# PathFinder_1.net
KiCad netlist of a schematic drawn in EasyEDA Pro
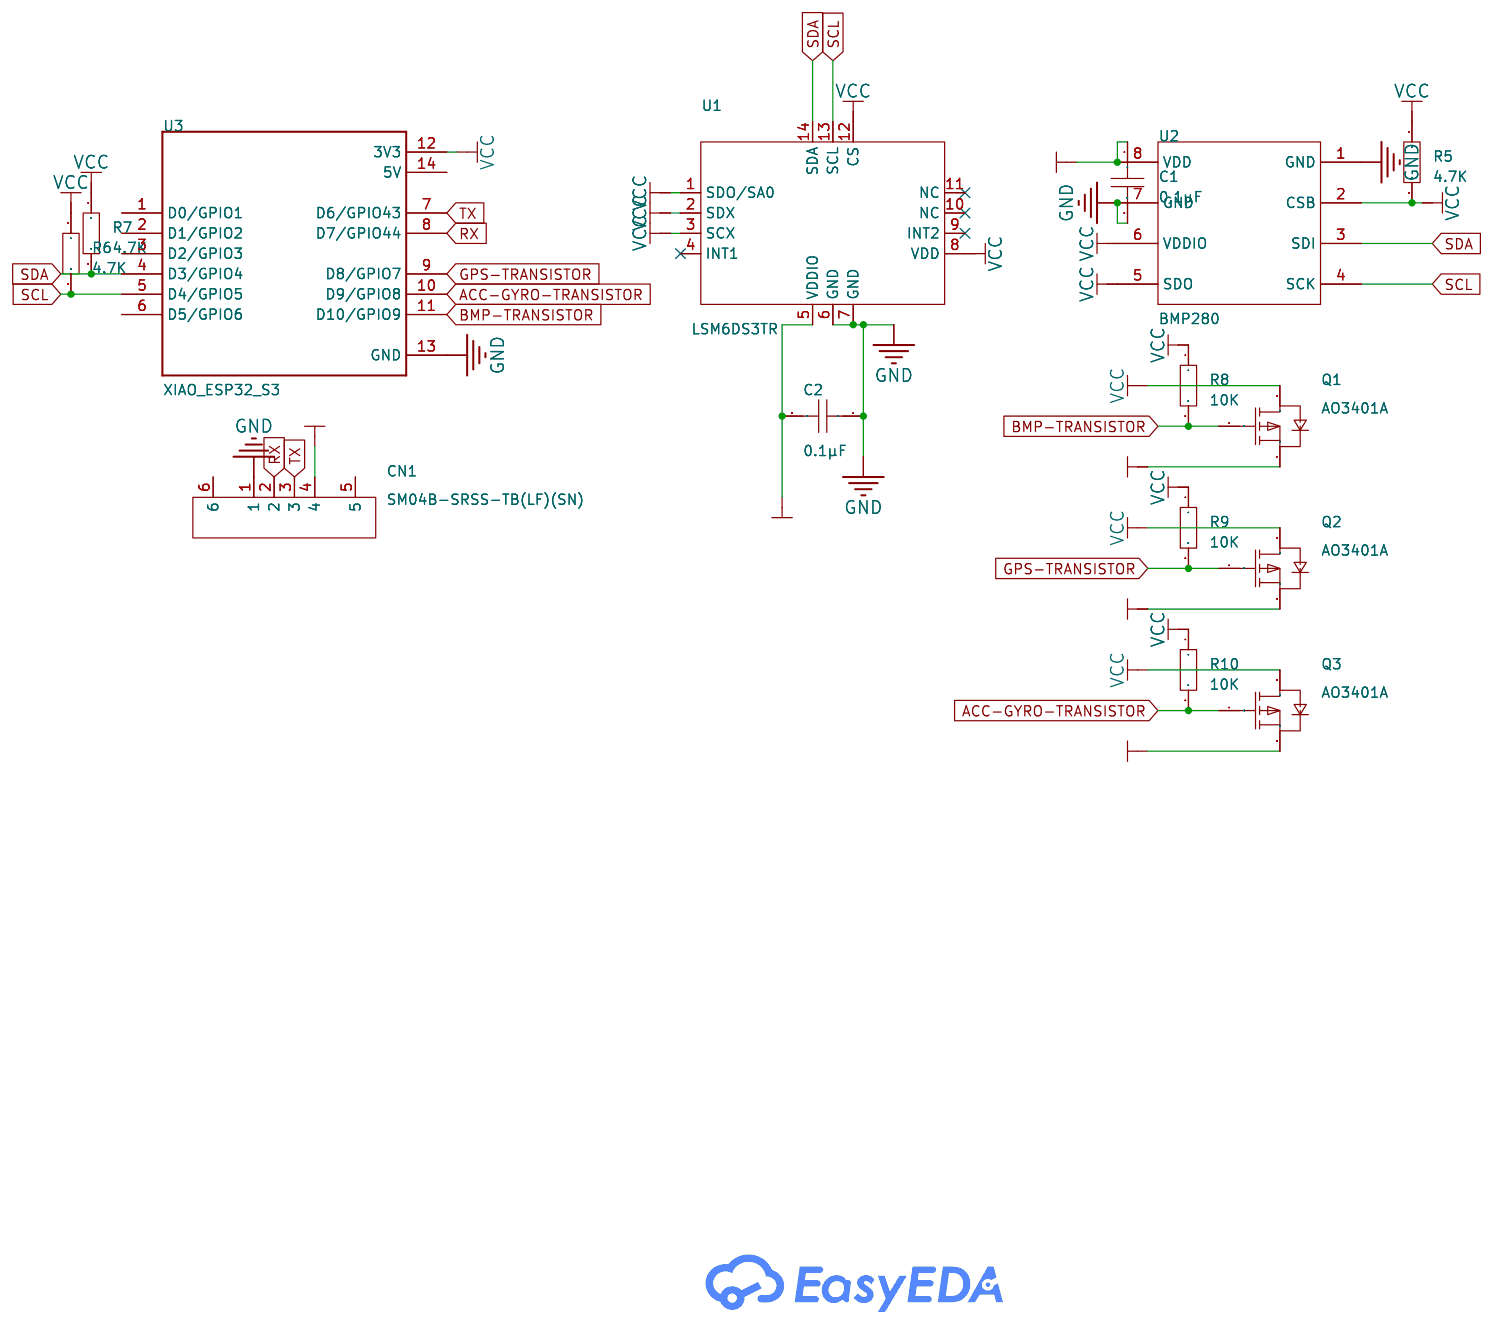
[diagram p0: schematic sheet]

(export (version "E")
  (design (tool "Eeschema 10.0.6"))
  (components
    (comp (ref "C1")
      (value "100nF")
      (footprint "easyedapro:C0603")
      (libsource (lib "easyedapro") (part "CAP"))
    )
    (comp (ref "C2")
      (value "100nF")
      (footprint "easyedapro:C0603")
      (libsource (lib "easyedapro") (part "CAP"))
    )
    (comp (ref "CN1")
      (value "SM04B-SRSS-TB(LF)(SN)")
      (footprint "easyedapro:CONN-SMD_4P-P1.00_SM04B-SRSS-TB-LF-SN")
      (fields (field (name "Manufacturer") "JST"))
      (libsource (lib "easyedapro") (part "SM04B-SRSS-TB (LF)(SN)"))
    )
    (comp (ref "Q1")
      (value "AO3401A")
      (footprint "easyedapro:SOT-23-3_L2.9-W1.3-P1.90-LS2.4-BR")
      (fields (field (name "Manufacturer") "YTL(亚特联)"))
      (libsource (lib "easyedapro") (part "AO3401A_C53477312"))
    )
    (comp (ref "Q2")
      (value "AO3401A")
      (footprint "easyedapro:SOT-23-3_L2.9-W1.3-P1.90-LS2.4-BR")
      (fields (field (name "Manufacturer") "YTL(亚特联)"))
      (libsource (lib "easyedapro") (part "AO3401A_C53477312"))
    )
    (comp (ref "Q3")
      (value "AO3401A")
      (footprint "easyedapro:SOT-23-3_L2.9-W1.3-P1.90-LS2.4-BR")
      (fields (field (name "Manufacturer") "YTL(亚特联)"))
      (libsource (lib "easyedapro") (part "AO3401A_C53477312"))
    )
    (comp (ref "R5") (value "10K") (footprint "easyedapro:R0603") (libsource (lib "easyedapro") (part "Res")))
    (comp (ref "R6") (value "10K") (footprint "easyedapro:R0603") (libsource (lib "easyedapro") (part "Res")))
    (comp (ref "R7") (value "10K") (footprint "easyedapro:R0603") (libsource (lib "easyedapro") (part "Res")))
    (comp (ref "R8") (value "10K") (footprint "easyedapro:R0603") (libsource (lib "easyedapro") (part "Res")))
    (comp (ref "R9") (value "10K") (footprint "easyedapro:R0603") (libsource (lib "easyedapro") (part "Res")))
    (comp (ref "R10")
      (value "10K")
      (footprint "easyedapro:R0603")
      (libsource (lib "easyedapro") (part "Res"))
    )
    (comp (ref "U1")
      (value "LSM6DS3TR")
      (footprint "easyedapro:LGA-14_L3.0-W2.5-P0.50-TL")
      (fields (field (name "Manufacturer") "ST(意法半导体)"))
      (libsource (lib "easyedapro") (part "LSM6DS3TR"))
    )
    (comp (ref "U2")
      (value "BMP280")
      (footprint "easyedapro:LGA-8_L2.5-W2.0-P0.65_AMP6127")
      (fields (field (name "Manufacturer") "Bosch(博世)"))
      (libsource (lib "easyedapro") (part "BMP280"))
    )
    (comp (ref "U3")
      (value "XIAO_ESP32_S3")
      (footprint "easyedapro:MODULE_XIAO_ESP32_S3")
      (libsource (lib "easyedapro") (part "XIAO_ESP32_S3"))
    )
  )
  (nets
    (net (code "1") (name "ACC-GYRO-TRANSISTOR") (class "Default")
      (node (ref "Q3") (pin "1") (pinfunction "G_1") (pintype "unspecified"))
      (node (ref "R10") (pin "2") (pinfunction "2_2") (pintype "input"))
      (node (ref "U3") (pin "10") (pinfunction "D9/GPIO8_10") (pintype "bidirectional"))
    )
    (net (code "2") (name "BMP-TRANSISTOR") (class "Default")
      (node (ref "Q1") (pin "1") (pinfunction "G_1") (pintype "unspecified"))
      (node (ref "R8") (pin "2") (pinfunction "2_2") (pintype "input"))
      (node (ref "U3") (pin "11") (pinfunction "D10/GPIO9_11") (pintype "bidirectional"))
    )
    (net (code "3") (name "GND") (class "Default")
      (node (ref "C1") (pin "2") (pinfunction "2_2") (pintype "input"))
      (node (ref "C2") (pin "1") (pinfunction "1_1") (pintype "input"))
      (node (ref "CN1") (pin "1") (pinfunction "1_1") (pintype "unspecified"))
      (node (ref "U1") (pin "6") (pinfunction "GND_6") (pintype "unspecified"))
      (node (ref "U1") (pin "7") (pinfunction "GND_7") (pintype "unspecified"))
      (node (ref "U2") (pin "1") (pinfunction "GND_1") (pintype "unspecified"))
      (node (ref "U2") (pin "7") (pinfunction "GND_7") (pintype "unspecified"))
      (node (ref "U3") (pin "13") (pinfunction "GND_13") (pintype "unspecified"))
    )
    (net (code "4") (name "GPS-TRANSISTOR") (class "Default")
      (node (ref "Q2") (pin "1") (pinfunction "G_1") (pintype "unspecified"))
      (node (ref "R9") (pin "2") (pinfunction "2_2") (pintype "input"))
      (node (ref "U3") (pin "9") (pinfunction "D8/GPIO7_9") (pintype "bidirectional"))
    )
    (net (code "5") (name "RX") (class "Default")
      (node (ref "CN1") (pin "2") (pinfunction "2_2") (pintype "unspecified"))
      (node (ref "U3") (pin "8") (pinfunction "D7/GPIO44_8") (pintype "bidirectional"))
    )
    (net (code "6") (name "SCL") (class "Default")
      (node (ref "R6") (pin "2") (pinfunction "2_2") (pintype "input"))
      (node (ref "U1") (pin "13") (pinfunction "SCL_13") (pintype "unspecified"))
      (node (ref "U2") (pin "4") (pinfunction "SCK_4") (pintype "unspecified"))
      (node (ref "U3") (pin "5") (pinfunction "D4/GPIO5_5") (pintype "bidirectional"))
    )
    (net (code "7") (name "SDA") (class "Default")
      (node (ref "R7") (pin "2") (pinfunction "2_2") (pintype "input"))
      (node (ref "U1") (pin "14") (pinfunction "SDA_14") (pintype "unspecified"))
      (node (ref "U2") (pin "3") (pinfunction "SDI_3") (pintype "unspecified"))
      (node (ref "U3") (pin "4") (pinfunction "D3/GPIO4_4") (pintype "bidirectional"))
    )
    (net (code "8") (name "TX") (class "Default")
      (node (ref "CN1") (pin "3") (pinfunction "3_3") (pintype "unspecified"))
      (node (ref "U3") (pin "7") (pinfunction "D6/GPIO43_7") (pintype "bidirectional"))
    )
    (net (code "9") (name "VCC") (class "Default")
      (node (ref "Q1") (pin "3") (pinfunction "D_3") (pintype "unspecified"))
      (node (ref "Q2") (pin "3") (pinfunction "D_3") (pintype "unspecified"))
      (node (ref "Q3") (pin "3") (pinfunction "D_3") (pintype "unspecified"))
      (node (ref "R10") (pin "1") (pinfunction "1_1") (pintype "input"))
      (node (ref "R5") (pin "1") (pinfunction "1_1") (pintype "input"))
      (node (ref "R5") (pin "2") (pinfunction "2_2") (pintype "input"))
      (node (ref "R6") (pin "1") (pinfunction "1_1") (pintype "input"))
      (node (ref "R7") (pin "1") (pinfunction "1_1") (pintype "input"))
      (node (ref "R8") (pin "1") (pinfunction "1_1") (pintype "input"))
      (node (ref "R9") (pin "1") (pinfunction "1_1") (pintype "input"))
      (node (ref "U1") (pin "1") (pinfunction "SDO/SA0_1") (pintype "unspecified"))
      (node (ref "U1") (pin "12") (pinfunction "CS_12") (pintype "unspecified"))
      (node (ref "U1") (pin "2") (pinfunction "SDX_2") (pintype "unspecified"))
      (node (ref "U1") (pin "3") (pinfunction "SCX_3") (pintype "unspecified"))
      (node (ref "U1") (pin "8") (pinfunction "VDD_8") (pintype "unspecified"))
      (node (ref "U2") (pin "2") (pinfunction "CSB_2") (pintype "unspecified"))
      (node (ref "U2") (pin "5") (pinfunction "SDO_5") (pintype "unspecified"))
      (node (ref "U2") (pin "6") (pinfunction "VDDIO_6") (pintype "unspecified"))
      (node (ref "U3") (pin "12") (pinfunction "3V3_12") (pintype "unspecified"))
    )
    (net (code "10") (name "VCC-BMP") (class "Default")
      (node (ref "C1") (pin "1") (pinfunction "1_1") (pintype "input"))
      (node (ref "Q1") (pin "2") (pinfunction "S_2") (pintype "unspecified"))
      (node (ref "U2") (pin "8") (pinfunction "VDD_8") (pintype "unspecified"))
    )
    (net (code "11") (name "VCC-GPS") (class "Default")
      (node (ref "CN1") (pin "4") (pinfunction "4_4") (pintype "unspecified"))
      (node (ref "Q2") (pin "2") (pinfunction "S_2") (pintype "unspecified"))
    )
    (net (code "12") (name "VCC-GYRO-ACC") (class "Default")
      (node (ref "C2") (pin "2") (pinfunction "2_2") (pintype "input"))
      (node (ref "Q3") (pin "2") (pinfunction "S_2") (pintype "unspecified"))
      (node (ref "U1") (pin "5") (pinfunction "VDDIO_5") (pintype "unspecified"))
    )
    (net (code "13") (name "unconnected-(CN1-Pad5)") (class "Default")
      (node (ref "CN1") (pin "5") (pinfunction "5_5") (pintype "unspecified"))
    )
    (net (code "14") (name "unconnected-(CN1-Pad6)") (class "Default")
      (node (ref "CN1") (pin "6") (pinfunction "6_6") (pintype "unspecified"))
    )
    (net (code "15") (name "unconnected-(U1-INT1-Pad4)") (class "Default")
      (node (ref "U1") (pin "4") (pinfunction "INT1_4") (pintype "unspecified+no_connect"))
    )
    (net (code "16") (name "unconnected-(U1-INT2-Pad9)") (class "Default")
      (node (ref "U1") (pin "9") (pinfunction "INT2_9") (pintype "unspecified+no_connect"))
    )
    (net (code "17") (name "unconnected-(U1-NC-Pad10)") (class "Default")
      (node (ref "U1") (pin "10") (pinfunction "NC_10") (pintype "unspecified+no_connect"))
    )
    (net (code "18") (name "unconnected-(U1-NC-Pad11)") (class "Default")
      (node (ref "U1") (pin "11") (pinfunction "NC_11") (pintype "unspecified+no_connect"))
    )
    (net (code "19") (name "unconnected-(U3-5V-Pad14)") (class "Default")
      (node (ref "U3") (pin "14") (pinfunction "5V_14") (pintype "unspecified"))
    )
    (net (code "20") (name "unconnected-(U3-D0{slash}GPIO1-Pad1)") (class "Default")
      (node (ref "U3") (pin "1") (pinfunction "D0/GPIO1_1") (pintype "bidirectional"))
    )
    (net (code "21") (name "unconnected-(U3-D1{slash}GPIO2-Pad2)") (class "Default")
      (node (ref "U3") (pin "2") (pinfunction "D1/GPIO2_2") (pintype "bidirectional"))
    )
    (net (code "22") (name "unconnected-(U3-D2{slash}GPIO3-Pad3)") (class "Default")
      (node (ref "U3") (pin "3") (pinfunction "D2/GPIO3_3") (pintype "bidirectional"))
    )
    (net (code "23") (name "unconnected-(U3-D5{slash}GPIO6-Pad6)") (class "Default")
      (node (ref "U3") (pin "6") (pinfunction "D5/GPIO6_6") (pintype "bidirectional"))
    )
  )
)
